# 6024.net
KiCad netlist of a schematic drawn in EasyEDA Pro
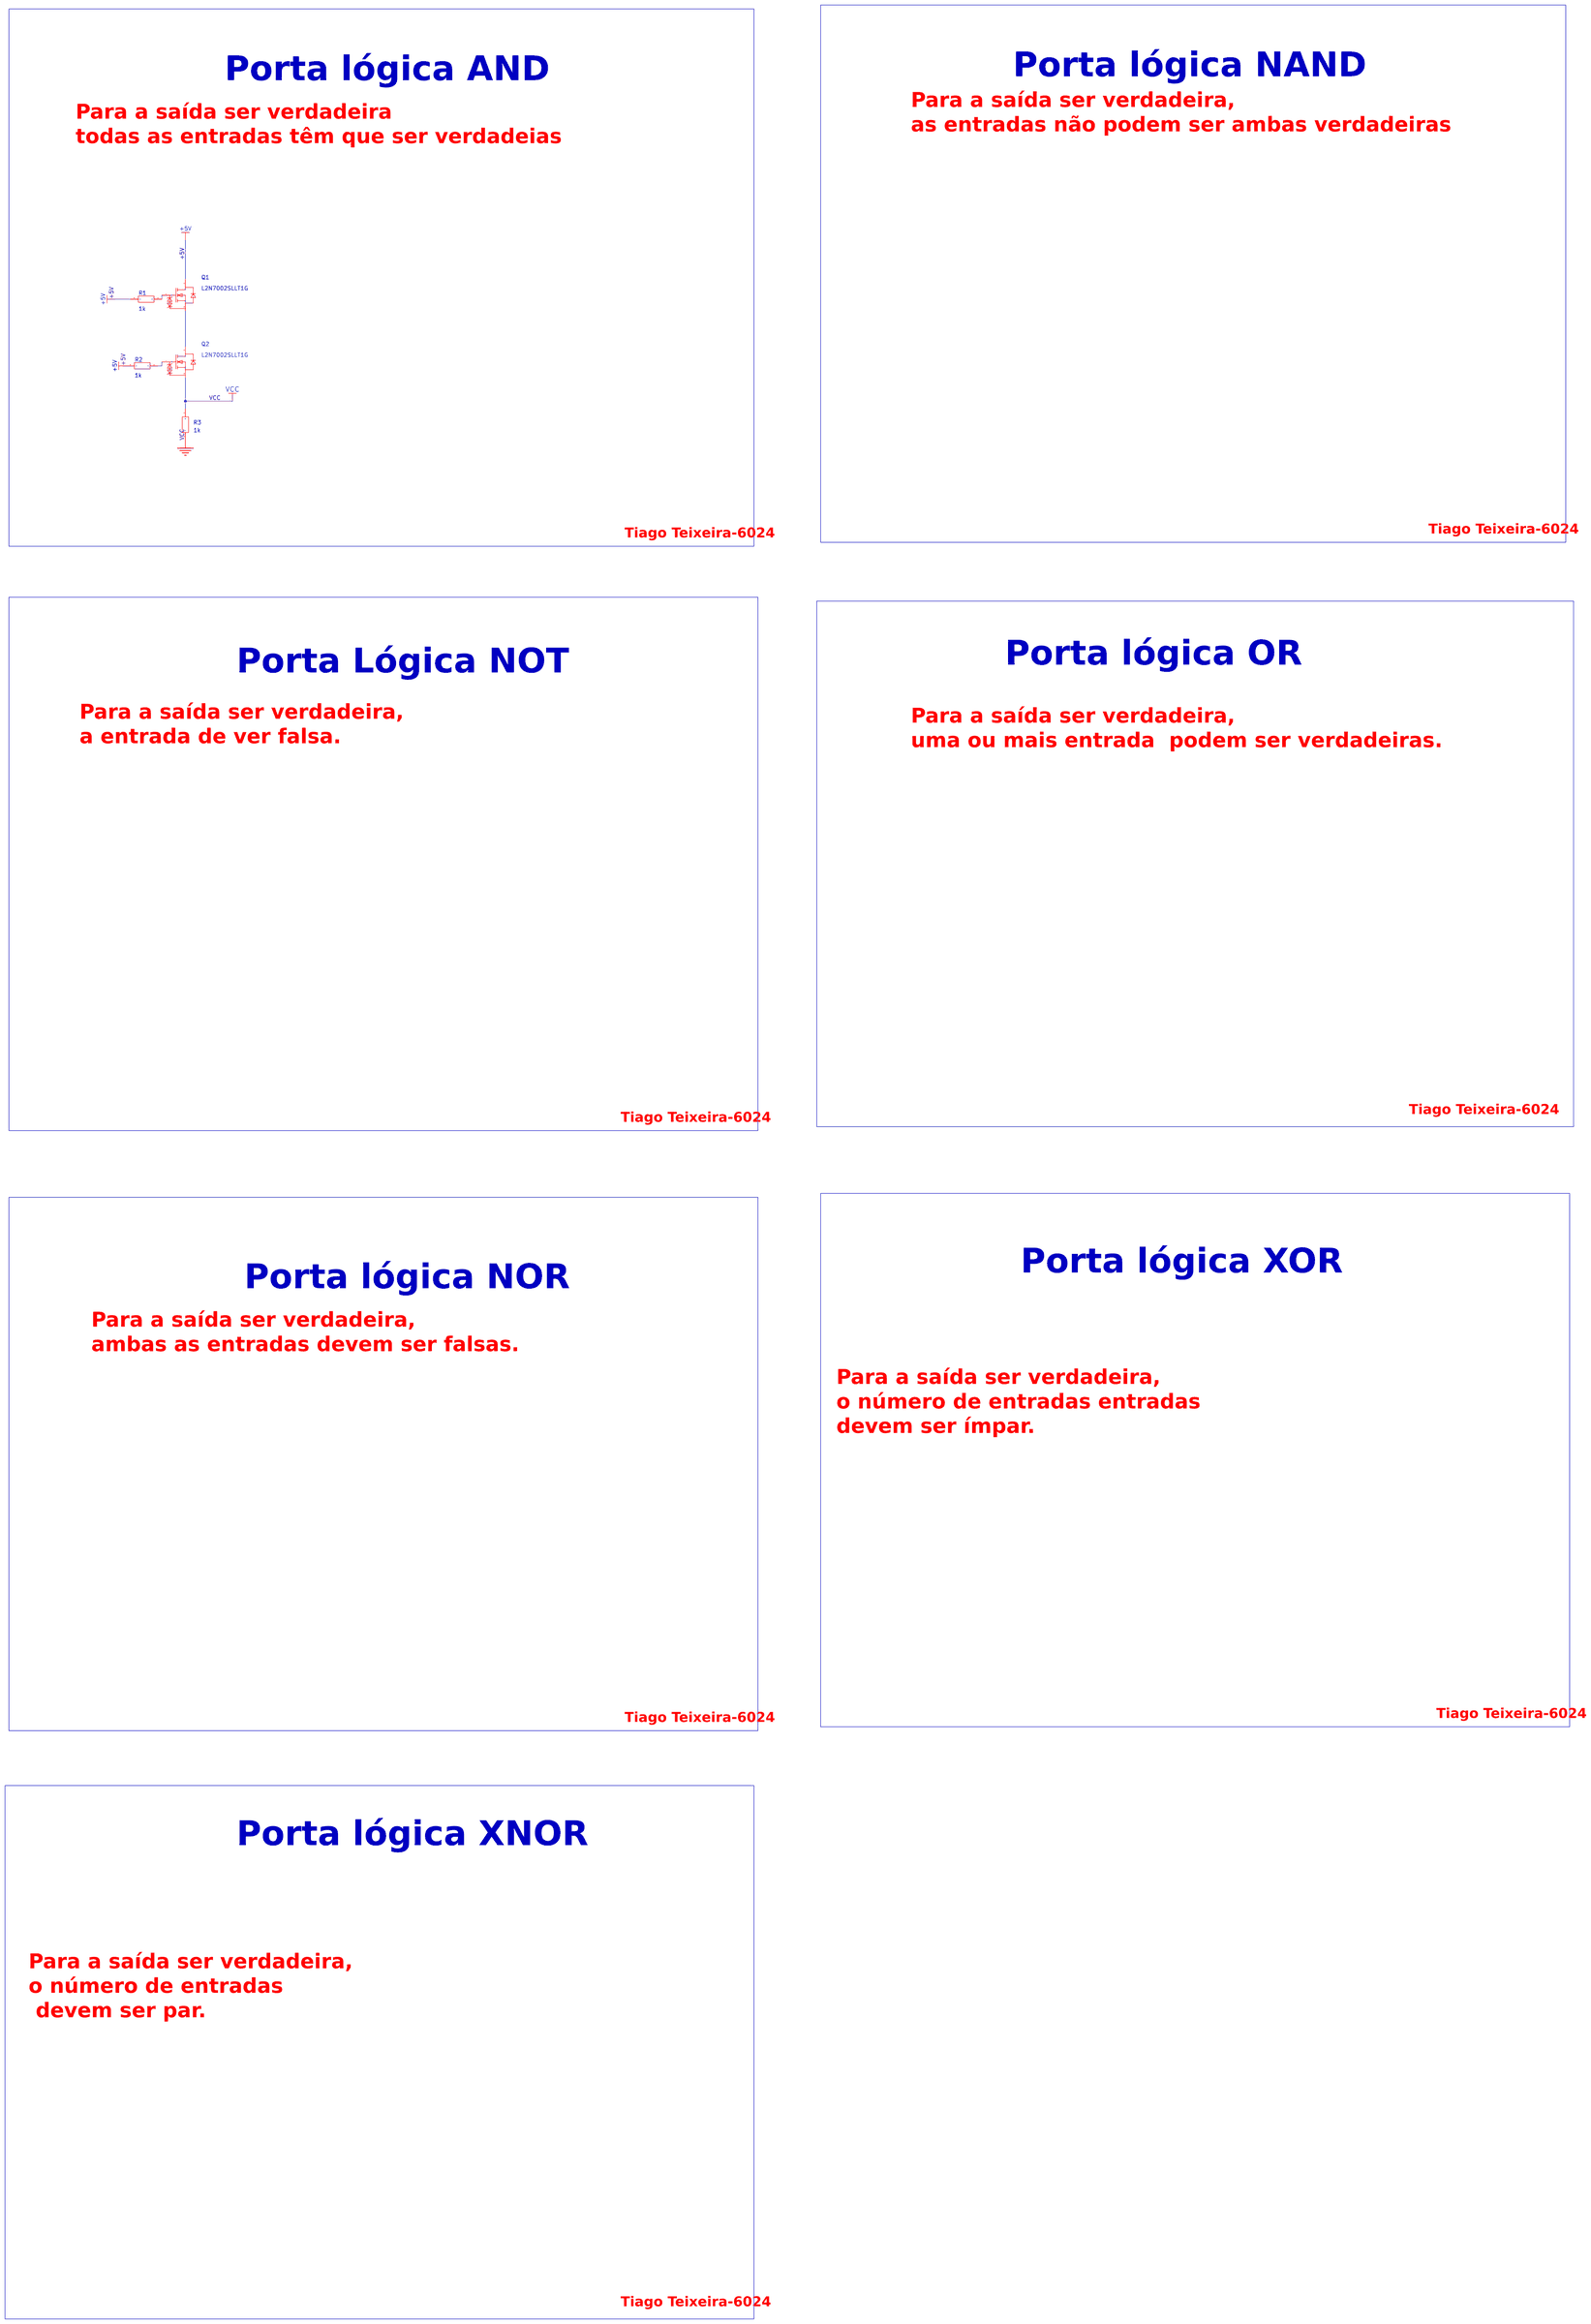
[diagram p0: schematic sheet]

(export (version "E")
  (design (tool "Eeschema 10.0.6"))
  (components
    (comp (ref "Q1")
      (value "L2N7002SLLT1G")
      (footprint "easyedapro:SOT-23-3_L3.0-W1.7-P0.95-LS2.9-BR")
      (fields (field (name "Manufacturer") "LRC(乐山无线电)"))
      (libsource (lib "easyedapro") (part "L2N7002SLLT1G"))
    )
    (comp (ref "Q2")
      (value "L2N7002SLLT1G")
      (footprint "easyedapro:SOT-23-3_L3.0-W1.7-P0.95-LS2.9-BR")
      (fields (field (name "Manufacturer") "LRC(乐山无线电)"))
      (libsource (lib "easyedapro") (part "L2N7002SLLT1G"))
    )
    (comp (ref "R1") (value "10K") (footprint "easyedapro:R0603") (libsource (lib "easyedapro") (part "Res")))
    (comp (ref "R2") (value "10K") (footprint "easyedapro:R0603") (libsource (lib "easyedapro") (part "Res")))
    (comp (ref "R3") (value "10K") (footprint "easyedapro:R0603") (libsource (lib "easyedapro") (part "Res")))
  )
  (nets
    (net (code "1") (name "+5V") (class "Default")
      (node (ref "Q1") (pin "3") (pinfunction "D_3") (pintype "unspecified"))
      (node (ref "R1") (pin "2") (pinfunction "2_2") (pintype "input"))
      (node (ref "R2") (pin "2") (pinfunction "2_2") (pintype "input"))
    )
    (net (code "2") (name "Net-(Q1-G)") (class "Default")
      (node (ref "Q1") (pin "1") (pinfunction "G_1") (pintype "unspecified"))
      (node (ref "R1") (pin "1") (pinfunction "1_1") (pintype "input"))
    )
    (net (code "3") (name "Net-(Q1-S)") (class "Default")
      (node (ref "Q1") (pin "2") (pinfunction "S_2") (pintype "unspecified"))
      (node (ref "Q2") (pin "3") (pinfunction "D_3") (pintype "unspecified"))
    )
    (net (code "4") (name "Net-(Q2-G)") (class "Default")
      (node (ref "Q2") (pin "1") (pinfunction "G_1") (pintype "unspecified"))
      (node (ref "R2") (pin "1") (pinfunction "1_1") (pintype "input"))
    )
    (net (code "5") (name "VCC") (class "Default")
      (node (ref "Q2") (pin "2") (pinfunction "S_2") (pintype "unspecified"))
      (node (ref "R3") (pin "1") (pinfunction "1_1") (pintype "input"))
      (node (ref "R3") (pin "2") (pinfunction "2_2") (pintype "input"))
    )
  )
)
